# Bluetooth.net
KiCad netlist of a schematic drawn in Altium Designer
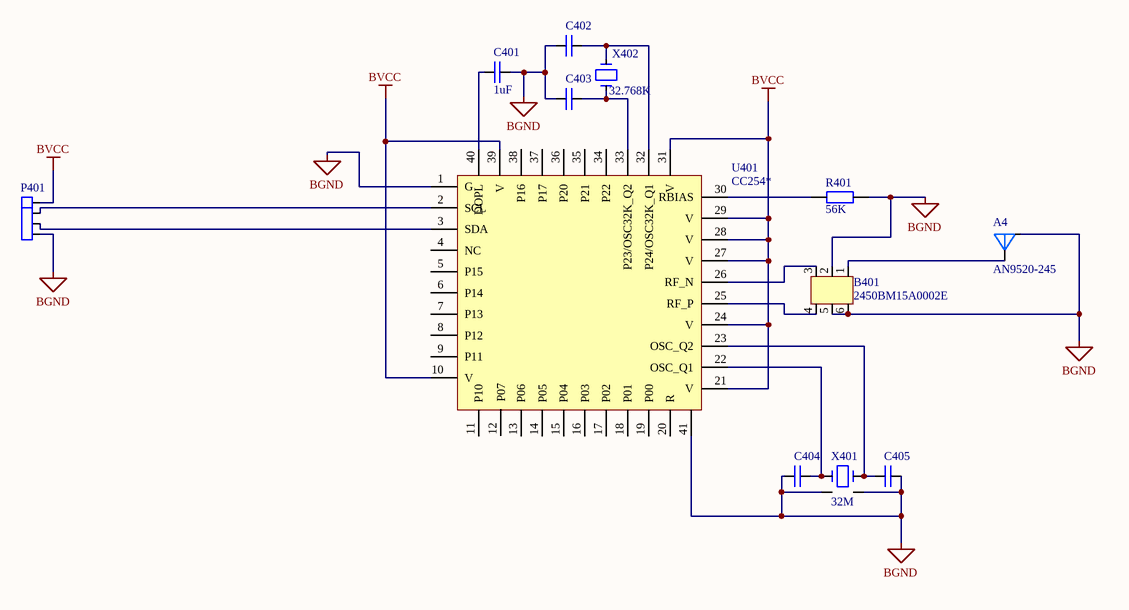
[diagram p0: Bluetooth.SchDoc]

(export (version "E")
  (design (tool "Eeschema 10.0.6"))
  (components
    (comp (ref "A4")
      (value "AN9520-245")
      (footprint "AN9520-245")
      (description "antenna")
      (libsource (lib "Library") (part "AN9520-245"))
    )
    (comp (ref "B401")
      (value "2450BM15A0002E")
      (footprint "2450BM15A0002")
      (description "CC2541")
      (libsource (lib "Library") (part "2450BM15A0002E"))
    )
    (comp (ref "C401") (value "1uF") (footprint "0603") (libsource (lib "Library") (part "C0603")))
    (comp (ref "C402") (value "~") (footprint "0603") (libsource (lib "Library") (part "C0603")))
    (comp (ref "C403") (value "~") (footprint "0603") (libsource (lib "Library") (part "C0603")))
    (comp (ref "C404") (value "~") (footprint "0603") (libsource (lib "Library") (part "C0603")))
    (comp (ref "C405") (value "~") (footprint "0603") (libsource (lib "Library") (part "C0603")))
    (comp (ref "P401") (value "DIP_4") (footprint "DIP_4") (libsource (lib "Library") (part "DIP_4")))
    (comp (ref "R401") (value "56K") (footprint "0603") (libsource (lib "Library") (part "R0603")))
    (comp (ref "U401") (value "CC254*") (footprint "CC254x") (libsource (lib "Library") (part "CC254x")))
    (comp (ref "X401")
      (value "32M")
      (footprint "3225")
      (description "3225")
      (libsource (lib "Library") (part "X2"))
    )
    (comp (ref "X402")
      (value "32.768K")
      (footprint "3215")
      (description "3215")
      (libsource (lib "Library") (part "X3"))
    )
  )
  (nets
    (net (code "1") (name "BGND") (class "Default")
      (node (ref "A4") (pin "2") (pinfunction "2_2") (pintype "passive"))
      (node (ref "B401") (pin "2") (pinfunction "2_2") (pintype "passive"))
      (node (ref "B401") (pin "5") (pinfunction "5_5") (pintype "passive"))
      (node (ref "B401") (pin "6") (pinfunction "6_6") (pintype "passive"))
      (node (ref "C401") (pin "2") (pinfunction "2_2") (pintype "passive"))
      (node (ref "C402") (pin "1") (pinfunction "1_1") (pintype "passive"))
      (node (ref "C403") (pin "1") (pinfunction "1_1") (pintype "passive"))
      (node (ref "C404") (pin "1") (pinfunction "1_1") (pintype "passive"))
      (node (ref "C405") (pin "2") (pinfunction "2_2") (pintype "passive"))
      (node (ref "P401") (pin "4") (pinfunction "4_4") (pintype "passive"))
      (node (ref "R401") (pin "1") (pinfunction "1_1") (pintype "passive"))
      (node (ref "U401") (pin "1") (pinfunction "G_1") (pintype "passive"))
      (node (ref "U401") (pin "41") (pinfunction "41_41") (pintype "passive"))
      (node (ref "X401") (pin "2") (pinfunction "2_2") (pintype "passive"))
      (node (ref "X401") (pin "4") (pinfunction "4_4") (pintype "passive"))
    )
    (net (code "2") (name "BVCC") (class "Default")
      (node (ref "P401") (pin "1") (pinfunction "1_1") (pintype "passive"))
      (node (ref "U401") (pin "10") (pinfunction "V_10") (pintype "passive"))
      (node (ref "U401") (pin "21") (pinfunction "V_21") (pintype "passive"))
      (node (ref "U401") (pin "24") (pinfunction "V_24") (pintype "passive"))
      (node (ref "U401") (pin "27") (pinfunction "V_27") (pintype "passive"))
      (node (ref "U401") (pin "28") (pinfunction "V_28") (pintype "passive"))
      (node (ref "U401") (pin "29") (pinfunction "V_29") (pintype "passive"))
      (node (ref "U401") (pin "31") (pinfunction "V_31") (pintype "passive"))
      (node (ref "U401") (pin "39") (pinfunction "V_39") (pintype "passive"))
    )
    (net (code "3") (name "Net-(A4-Pad1)") (class "Default")
      (node (ref "A4") (pin "1") (pinfunction "1_1") (pintype "passive"))
      (node (ref "B401") (pin "1") (pinfunction "1_1") (pintype "passive"))
    )
    (net (code "4") (name "Net-(U401-DOPL)") (class "Default")
      (node (ref "C401") (pin "1") (pinfunction "1_1") (pintype "passive"))
      (node (ref "U401") (pin "40") (pinfunction "DOPL_40") (pintype "passive"))
    )
    (net (code "5") (name "Net-(U401-OSC_Q1)") (class "Default")
      (node (ref "C404") (pin "2") (pinfunction "2_2") (pintype "passive"))
      (node (ref "U401") (pin "22") (pinfunction "OSC_Q1_22") (pintype "passive"))
      (node (ref "X401") (pin "1") (pintype "passive"))
    )
    (net (code "6") (name "Net-(U401-OSC_Q2)") (class "Default")
      (node (ref "C405") (pin "1") (pinfunction "1_1") (pintype "passive"))
      (node (ref "U401") (pin "23") (pinfunction "OSC_Q2_23") (pintype "passive"))
      (node (ref "X401") (pin "3") (pintype "passive"))
    )
    (net (code "7") (name "Net-(U401-P23{slash}OSC32K_Q2)") (class "Default")
      (node (ref "C403") (pin "2") (pinfunction "2_2") (pintype "passive"))
      (node (ref "U401") (pin "33") (pinfunction "P23/OSC32K_Q2_33") (pintype "passive"))
      (node (ref "X402") (pin "1") (pintype "passive"))
    )
    (net (code "8") (name "Net-(U401-P24{slash}OSC32K_Q1)") (class "Default")
      (node (ref "C402") (pin "2") (pinfunction "2_2") (pintype "passive"))
      (node (ref "U401") (pin "32") (pinfunction "P24/OSC32K_Q1_32") (pintype "passive"))
      (node (ref "X402") (pin "2") (pintype "passive"))
    )
    (net (code "9") (name "Net-(U401-RBIAS)") (class "Default")
      (node (ref "R401") (pin "2") (pinfunction "2_2") (pintype "passive"))
      (node (ref "U401") (pin "30") (pinfunction "RBIAS_30") (pintype "passive"))
    )
    (net (code "10") (name "Net-(U401-RF_N)") (class "Default")
      (node (ref "B401") (pin "3") (pinfunction "3_3") (pintype "passive"))
      (node (ref "U401") (pin "26") (pinfunction "RF_N_26") (pintype "passive"))
    )
    (net (code "11") (name "Net-(U401-RF_P)") (class "Default")
      (node (ref "B401") (pin "4") (pinfunction "4_4") (pintype "passive"))
      (node (ref "U401") (pin "25") (pinfunction "RF_P_25") (pintype "passive"))
    )
    (net (code "12") (name "Net-(U401-SCL)") (class "Default")
      (node (ref "P401") (pin "2") (pinfunction "2_2") (pintype "passive"))
      (node (ref "U401") (pin "2") (pinfunction "SCL_2") (pintype "passive"))
    )
    (net (code "13") (name "Net-(U401-SDA)") (class "Default")
      (node (ref "P401") (pin "3") (pinfunction "3_3") (pintype "passive"))
      (node (ref "U401") (pin "3") (pinfunction "SDA_3") (pintype "passive"))
    )
    (net (code "14") (name "unconnected-(U401-NC-Pad4)") (class "Default")
      (node (ref "U401") (pin "4") (pinfunction "NC_4") (pintype "passive"))
    )
    (net (code "15") (name "unconnected-(U401-P00-Pad19)") (class "Default")
      (node (ref "U401") (pin "19") (pinfunction "P00_19") (pintype "passive"))
    )
    (net (code "16") (name "unconnected-(U401-P01-Pad18)") (class "Default")
      (node (ref "U401") (pin "18") (pinfunction "P01_18") (pintype "passive"))
    )
    (net (code "17") (name "unconnected-(U401-P02-Pad17)") (class "Default")
      (node (ref "U401") (pin "17") (pinfunction "P02_17") (pintype "passive"))
    )
    (net (code "18") (name "unconnected-(U401-P03-Pad16)") (class "Default")
      (node (ref "U401") (pin "16") (pinfunction "P03_16") (pintype "passive"))
    )
    (net (code "19") (name "unconnected-(U401-P04-Pad15)") (class "Default")
      (node (ref "U401") (pin "15") (pinfunction "P04_15") (pintype "passive"))
    )
    (net (code "20") (name "unconnected-(U401-P05-Pad14)") (class "Default")
      (node (ref "U401") (pin "14") (pinfunction "P05_14") (pintype "passive"))
    )
    (net (code "21") (name "unconnected-(U401-P06-Pad13)") (class "Default")
      (node (ref "U401") (pin "13") (pinfunction "P06_13") (pintype "passive"))
    )
    (net (code "22") (name "unconnected-(U401-P07-Pad12)") (class "Default")
      (node (ref "U401") (pin "12") (pinfunction "P07_12") (pintype "passive"))
    )
    (net (code "23") (name "unconnected-(U401-P10-Pad11)") (class "Default")
      (node (ref "U401") (pin "11") (pinfunction "P10_11") (pintype "passive"))
    )
    (net (code "24") (name "unconnected-(U401-P11-Pad9)") (class "Default")
      (node (ref "U401") (pin "9") (pinfunction "P11_9") (pintype "passive"))
    )
    (net (code "25") (name "unconnected-(U401-P12-Pad8)") (class "Default")
      (node (ref "U401") (pin "8") (pinfunction "P12_8") (pintype "passive"))
    )
    (net (code "26") (name "unconnected-(U401-P13-Pad7)") (class "Default")
      (node (ref "U401") (pin "7") (pinfunction "P13_7") (pintype "passive"))
    )
    (net (code "27") (name "unconnected-(U401-P14-Pad6)") (class "Default")
      (node (ref "U401") (pin "6") (pinfunction "P14_6") (pintype "passive"))
    )
    (net (code "28") (name "unconnected-(U401-P15-Pad5)") (class "Default")
      (node (ref "U401") (pin "5") (pinfunction "P15_5") (pintype "passive"))
    )
    (net (code "29") (name "unconnected-(U401-P16-Pad38)") (class "Default")
      (node (ref "U401") (pin "38") (pinfunction "P16_38") (pintype "passive"))
    )
    (net (code "30") (name "unconnected-(U401-P17-Pad37)") (class "Default")
      (node (ref "U401") (pin "37") (pinfunction "P17_37") (pintype "passive"))
    )
    (net (code "31") (name "unconnected-(U401-P20-Pad36)") (class "Default")
      (node (ref "U401") (pin "36") (pinfunction "P20_36") (pintype "passive"))
    )
    (net (code "32") (name "unconnected-(U401-P21-Pad35)") (class "Default")
      (node (ref "U401") (pin "35") (pinfunction "P21_35") (pintype "passive"))
    )
    (net (code "33") (name "unconnected-(U401-P22-Pad34)") (class "Default")
      (node (ref "U401") (pin "34") (pinfunction "P22_34") (pintype "passive"))
    )
    (net (code "34") (name "unconnected-(U401-R-Pad20)") (class "Default")
      (node (ref "U401") (pin "20") (pinfunction "R_20") (pintype "passive"))
    )
  )
)
